# RH018_1.net
KiCad netlist of a schematic drawn in EAGLE
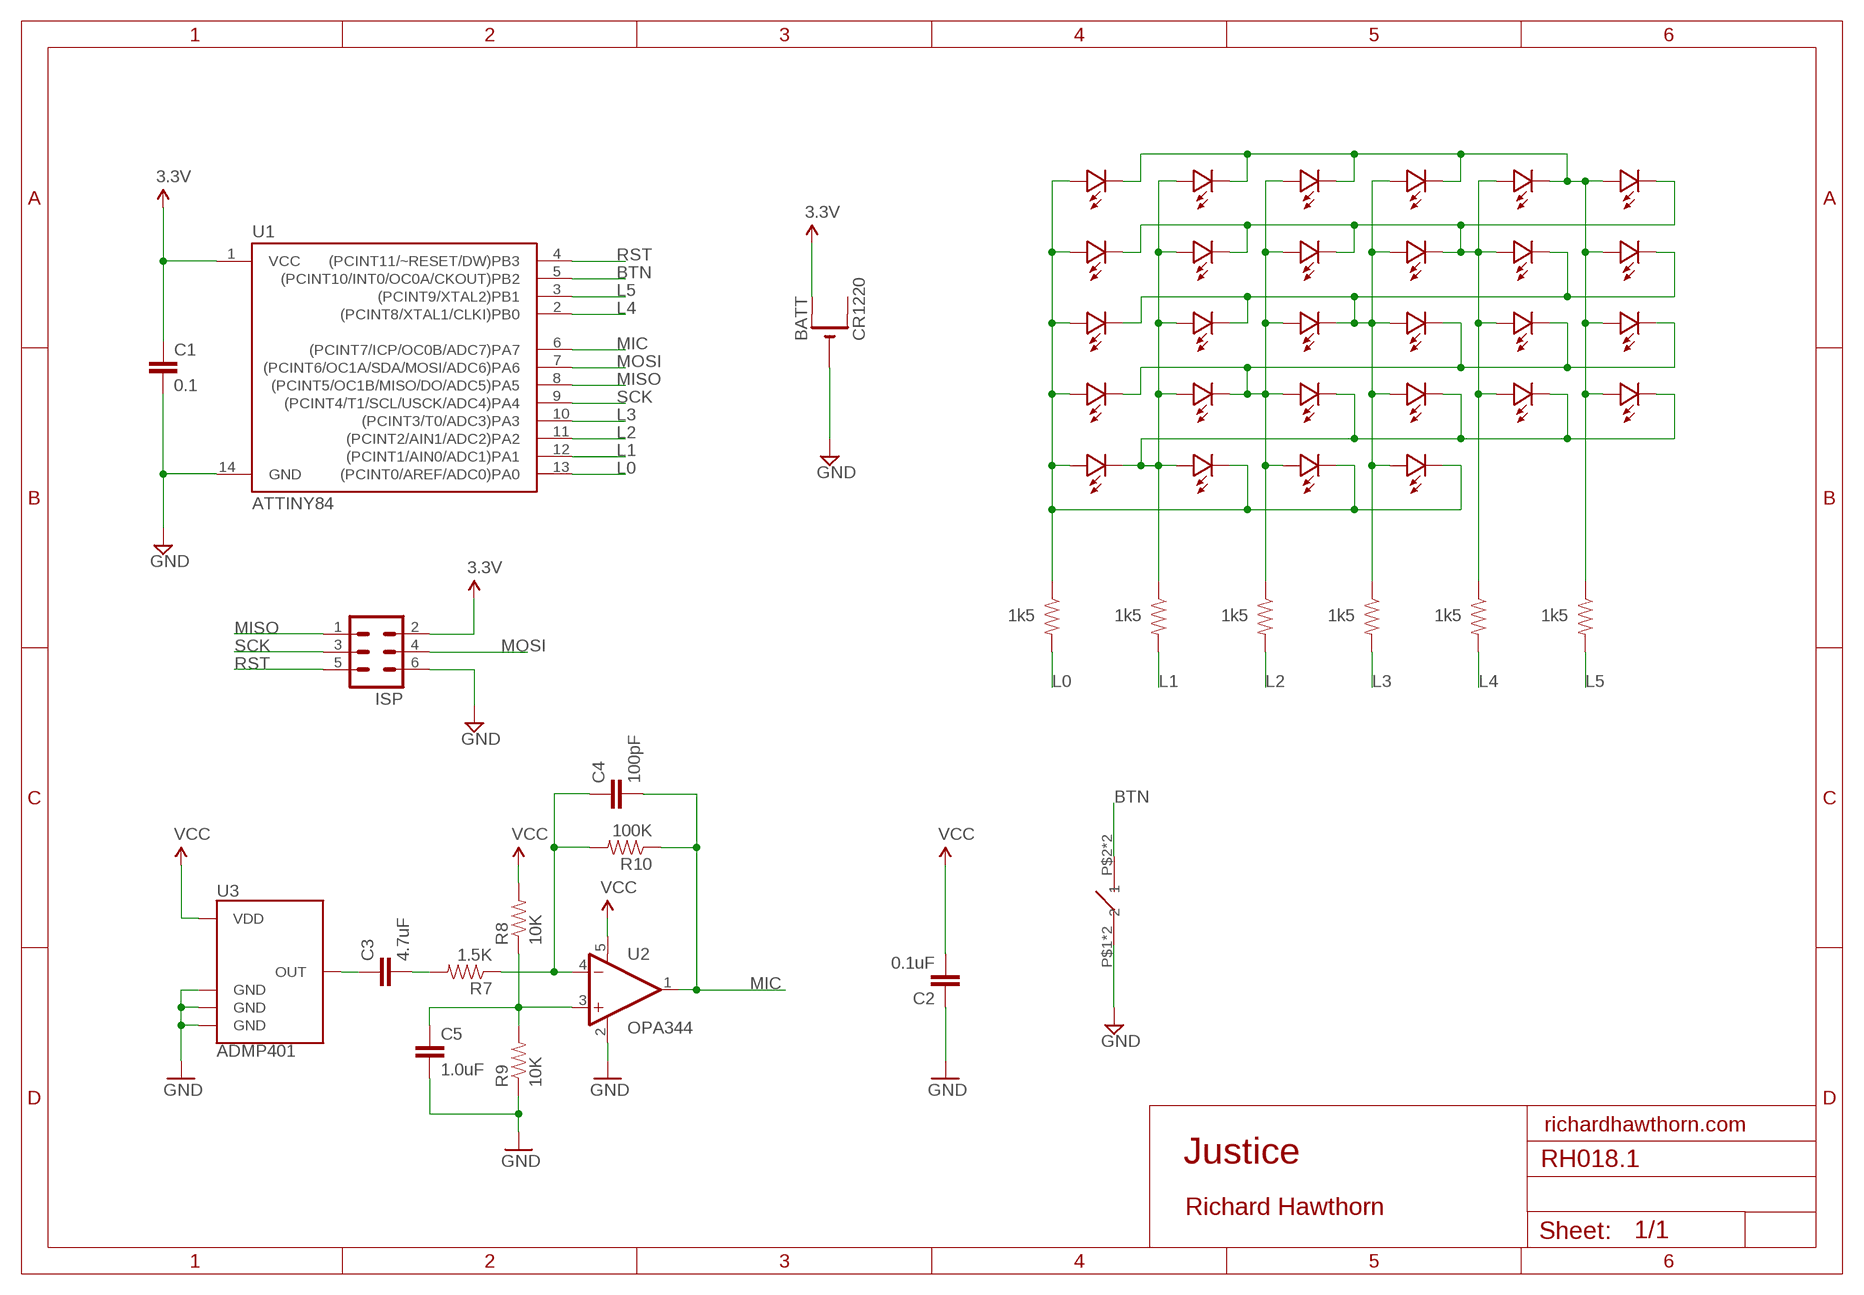
[diagram p0: schematic, sheet 1]

(export (version "E")
  (design (tool "Eeschema 10.0.6"))
  (components
    (comp (ref "BATT")
      (value "CR1220")
      (footprint "eagle-import:CR1220-SMD")
      (libsource (lib "eagle-import") (part "CR1220SMT"))
    )
    (comp (ref "BTN1")
      (value "TURTLE-3PIN")
      (footprint "eagle-import:TURTLE-3PIN")
      (libsource (lib "eagle-import") (part "TURTLE-3PIN"))
    )
    (comp (ref "C1")
      (value "0.1")
      (footprint "eagle-import:0603-CAP")
      (libsource (lib "eagle-import") (part "CAP0603-CAP"))
    )
    (comp (ref "C2")
      (value "0.1uF")
      (footprint "eagle-import:0402-CAP")
      (libsource (lib "eagle-import") (part "SparkFun_CAP0402-CAP"))
    )
    (comp (ref "C3")
      (value "4.7uF")
      (footprint "eagle-import:0402-CAP")
      (libsource (lib "eagle-import") (part "SparkFun_CAP0402-CAP"))
    )
    (comp (ref "C4")
      (value "100pF")
      (footprint "eagle-import:0402-CAP")
      (libsource (lib "eagle-import") (part "SparkFun_CAP0402-CAP"))
    )
    (comp (ref "C5")
      (value "1.0uF")
      (footprint "eagle-import:0402-CAP")
      (libsource (lib "eagle-import") (part "SparkFun_CAP0402-CAP"))
    )
    (comp (ref "ISP")
      (value "MA03-2")
      (footprint "eagle-import:MA03-2")
      (libsource (lib "eagle-import") (part "MA03-2"))
    )
    (comp (ref "LED1")
      (value "LED0603")
      (footprint "eagle-import:0603-LED")
      (libsource (lib "eagle-import") (part "LED0603"))
    )
    (comp (ref "LED2")
      (value "LED0603")
      (footprint "eagle-import:0603-LED")
      (libsource (lib "eagle-import") (part "LED0603"))
    )
    (comp (ref "LED3")
      (value "LED0603")
      (footprint "eagle-import:0603-LED")
      (libsource (lib "eagle-import") (part "LED0603"))
    )
    (comp (ref "LED4")
      (value "LED0603")
      (footprint "eagle-import:0603-LED")
      (libsource (lib "eagle-import") (part "LED0603"))
    )
    (comp (ref "LED5")
      (value "LED0603")
      (footprint "eagle-import:0603-LED")
      (libsource (lib "eagle-import") (part "LED0603"))
    )
    (comp (ref "LED6")
      (value "LED0603")
      (footprint "eagle-import:0603-LED")
      (libsource (lib "eagle-import") (part "LED0603"))
    )
    (comp (ref "LED7")
      (value "LED0603")
      (footprint "eagle-import:0603-LED")
      (libsource (lib "eagle-import") (part "LED0603"))
    )
    (comp (ref "LED8")
      (value "LED0603")
      (footprint "eagle-import:0603-LED")
      (libsource (lib "eagle-import") (part "LED0603"))
    )
    (comp (ref "LED9")
      (value "LED0603")
      (footprint "eagle-import:0603-LED")
      (libsource (lib "eagle-import") (part "LED0603"))
    )
    (comp (ref "LED10")
      (value "LED0603")
      (footprint "eagle-import:0603-LED")
      (libsource (lib "eagle-import") (part "LED0603"))
    )
    (comp (ref "LED11")
      (value "LED0603")
      (footprint "eagle-import:0603-LED")
      (libsource (lib "eagle-import") (part "LED0603"))
    )
    (comp (ref "LED12")
      (value "LED0603")
      (footprint "eagle-import:0603-LED")
      (libsource (lib "eagle-import") (part "LED0603"))
    )
    (comp (ref "LED13")
      (value "LED0603")
      (footprint "eagle-import:0603-LED")
      (libsource (lib "eagle-import") (part "LED0603"))
    )
    (comp (ref "LED14")
      (value "LED0603")
      (footprint "eagle-import:0603-LED")
      (libsource (lib "eagle-import") (part "LED0603"))
    )
    (comp (ref "LED15")
      (value "LED0603")
      (footprint "eagle-import:0603-LED")
      (libsource (lib "eagle-import") (part "LED0603"))
    )
    (comp (ref "LED16")
      (value "LED0603")
      (footprint "eagle-import:0603-LED")
      (libsource (lib "eagle-import") (part "LED0603"))
    )
    (comp (ref "LED17")
      (value "LED0603")
      (footprint "eagle-import:0603-LED")
      (libsource (lib "eagle-import") (part "LED0603"))
    )
    (comp (ref "LED18")
      (value "LED0603")
      (footprint "eagle-import:0603-LED")
      (libsource (lib "eagle-import") (part "LED0603"))
    )
    (comp (ref "LED19")
      (value "LED0603")
      (footprint "eagle-import:0603-LED")
      (libsource (lib "eagle-import") (part "LED0603"))
    )
    (comp (ref "LED20")
      (value "LED0603")
      (footprint "eagle-import:0603-LED")
      (libsource (lib "eagle-import") (part "LED0603"))
    )
    (comp (ref "LED21")
      (value "LED0603")
      (footprint "eagle-import:0603-LED")
      (libsource (lib "eagle-import") (part "LED0603"))
    )
    (comp (ref "LED22")
      (value "LED0603")
      (footprint "eagle-import:0603-LED")
      (libsource (lib "eagle-import") (part "LED0603"))
    )
    (comp (ref "LED23")
      (value "LED0603")
      (footprint "eagle-import:0603-LED")
      (libsource (lib "eagle-import") (part "LED0603"))
    )
    (comp (ref "LED24")
      (value "LED0603")
      (footprint "eagle-import:0603-LED")
      (libsource (lib "eagle-import") (part "LED0603"))
    )
    (comp (ref "LED25")
      (value "LED0603")
      (footprint "eagle-import:0603-LED")
      (libsource (lib "eagle-import") (part "LED0603"))
    )
    (comp (ref "LED26")
      (value "LED0603")
      (footprint "eagle-import:0603-LED")
      (libsource (lib "eagle-import") (part "LED0603"))
    )
    (comp (ref "LED27")
      (value "LED0603")
      (footprint "eagle-import:0603-LED")
      (libsource (lib "eagle-import") (part "LED0603"))
    )
    (comp (ref "LED28")
      (value "LED0603")
      (footprint "eagle-import:0603-LED")
      (libsource (lib "eagle-import") (part "LED0603"))
    )
    (comp (ref "R1")
      (value "1k5")
      (footprint "eagle-import:0603-RES")
      (libsource (lib "eagle-import") (part "RESISTOR0603-RES"))
    )
    (comp (ref "R2")
      (value "1k5")
      (footprint "eagle-import:0603-RES")
      (libsource (lib "eagle-import") (part "RESISTOR0603-RES"))
    )
    (comp (ref "R3")
      (value "1k5")
      (footprint "eagle-import:0603-RES")
      (libsource (lib "eagle-import") (part "RESISTOR0603-RES"))
    )
    (comp (ref "R4")
      (value "1k5")
      (footprint "eagle-import:0603-RES")
      (libsource (lib "eagle-import") (part "RESISTOR0603-RES"))
    )
    (comp (ref "R5")
      (value "1k5")
      (footprint "eagle-import:0603-RES")
      (libsource (lib "eagle-import") (part "RESISTOR0603-RES"))
    )
    (comp (ref "R6")
      (value "1k5")
      (footprint "eagle-import:0603-RES")
      (libsource (lib "eagle-import") (part "RESISTOR0603-RES"))
    )
    (comp (ref "R7")
      (value "1.5K")
      (footprint "eagle-import:0402-RES")
      (libsource (lib "eagle-import") (part "SparkFun_RESISTOR0402-RES"))
    )
    (comp (ref "R8")
      (value "10K")
      (footprint "eagle-import:0402-RES")
      (libsource (lib "eagle-import") (part "SparkFun_RESISTOR0402-RES"))
    )
    (comp (ref "R9")
      (value "10K")
      (footprint "eagle-import:0402-RES")
      (libsource (lib "eagle-import") (part "SparkFun_RESISTOR0402-RES"))
    )
    (comp (ref "R10")
      (value "100K")
      (footprint "eagle-import:0402-RES")
      (libsource (lib "eagle-import") (part "SparkFun_RESISTOR0402-RES"))
    )
    (comp (ref "U1")
      (value "ATTINY84")
      (footprint "eagle-import:SO14")
      (libsource (lib "eagle-import") (part "ATTINY84"))
    )
    (comp (ref "U2")
      (value "OPA344")
      (footprint "eagle-import:SOT23-5")
      (libsource (lib "eagle-import") (part "OPA344"))
    )
    (comp (ref "U3")
      (value "ADMP401")
      (footprint "eagle-import:ADMP401")
      (libsource (lib "eagle-import") (part "ADMP401"))
    )
  )
  (nets
    (net (code "1") (name "/BTN") (class "Default")
      (node (ref "BTN1") (pin "P$2") (pinfunction "2_P$2") (pintype "bidirectional"))
      (node (ref "BTN1") (pin "P$4") (pinfunction "2_P$4") (pintype "bidirectional"))
      (node (ref "U1") (pin "5") (pinfunction "(PCINT10/INT0/OC0A/CKOUT)PB2_5") (pintype "bidirectional"))
    )
    (net (code "2") (name "/L0") (class "Default")
      (node (ref "R1") (pin "2") (pinfunction "2_2") (pintype "passive"))
      (node (ref "U1") (pin "13") (pinfunction "(PCINT0/AREF/ADC0)PA0_13") (pintype "bidirectional"))
    )
    (net (code "3") (name "/L1") (class "Default")
      (node (ref "R2") (pin "2") (pinfunction "2_2") (pintype "passive"))
      (node (ref "U1") (pin "12") (pinfunction "(PCINT1/AIN0/ADC1)PA1_12") (pintype "bidirectional"))
    )
    (net (code "4") (name "/L2") (class "Default")
      (node (ref "R3") (pin "2") (pinfunction "2_2") (pintype "passive"))
      (node (ref "U1") (pin "11") (pinfunction "(PCINT2/AIN1/ADC2)PA2_11") (pintype "bidirectional"))
    )
    (net (code "5") (name "/L3") (class "Default")
      (node (ref "R4") (pin "2") (pinfunction "2_2") (pintype "passive"))
      (node (ref "U1") (pin "10") (pinfunction "(PCINT3/T0/ADC3)PA3_10") (pintype "bidirectional"))
    )
    (net (code "6") (name "/L4") (class "Default")
      (node (ref "R5") (pin "2") (pinfunction "2_2") (pintype "passive"))
      (node (ref "U1") (pin "2") (pinfunction "(PCINT8/XTAL1/CLKI)PB0_2") (pintype "bidirectional"))
    )
    (net (code "7") (name "/L5") (class "Default")
      (node (ref "R6") (pin "2") (pinfunction "2_2") (pintype "passive"))
      (node (ref "U1") (pin "3") (pinfunction "(PCINT9/XTAL2)PB1_3") (pintype "bidirectional"))
    )
    (net (code "8") (name "/MIC") (class "Default")
      (node (ref "C4") (pin "2") (pinfunction "2_2") (pintype "passive"))
      (node (ref "R10") (pin "1") (pinfunction "1_1") (pintype "passive"))
      (node (ref "U1") (pin "6") (pinfunction "(PCINT7/ICP/OC0B/ADC7)PA7_6") (pintype "bidirectional"))
      (node (ref "U2") (pin "1") (pinfunction "OUT_1") (pintype "output"))
    )
    (net (code "9") (name "/MISO") (class "Default")
      (node (ref "ISP") (pin "1") (pinfunction "1_1") (pintype "passive"))
      (node (ref "U1") (pin "8") (pinfunction "(PCINT5/OC1B/MISO/DO/ADC5)PA5_8") (pintype "bidirectional"))
    )
    (net (code "10") (name "/MOSI") (class "Default")
      (node (ref "ISP") (pin "4") (pinfunction "4_4") (pintype "passive"))
      (node (ref "U1") (pin "7") (pinfunction "(PCINT6/OC1A/SDA/MOSI/ADC6)PA6_7") (pintype "bidirectional"))
    )
    (net (code "11") (name "/RST") (class "Default")
      (node (ref "ISP") (pin "5") (pinfunction "5_5") (pintype "passive"))
      (node (ref "U1") (pin "4") (pinfunction "(PCINT11/~{RESET/DW})PB3_4") (pintype "bidirectional"))
    )
    (net (code "12") (name "/SCK") (class "Default")
      (node (ref "ISP") (pin "3") (pinfunction "3_3") (pintype "passive"))
      (node (ref "U1") (pin "9") (pinfunction "(PCINT4/T1/SCL/USCK/ADC4)PA4_9") (pintype "bidirectional"))
    )
    (net (code "13") (name "3.3V") (class "Default")
      (node (ref "BATT") (pin "+$1") (pinfunction "+_+$1") (pintype "passive"))
      (node (ref "C1") (pin "1") (pinfunction "1_1") (pintype "passive"))
      (node (ref "C2") (pin "2") (pinfunction "2_2") (pintype "passive"))
      (node (ref "ISP") (pin "2") (pinfunction "2_2") (pintype "passive"))
      (node (ref "R8") (pin "2") (pinfunction "2_2") (pintype "passive"))
      (node (ref "U1") (pin "1") (pinfunction "VCC_1") (pintype "bidirectional"))
      (node (ref "U2") (pin "5") (pinfunction "V+_5") (pintype "power_in"))
      (node (ref "U3") (pin "5") (pinfunction "VDD_5") (pintype "bidirectional"))
    )
    (net (code "14") (name "GND") (class "Default")
      (node (ref "BATT") (pin "-") (pinfunction "-_-") (pintype "passive"))
      (node (ref "BTN1") (pin "P$1") (pinfunction "1_P$1") (pintype "bidirectional"))
      (node (ref "BTN1") (pin "P$3") (pinfunction "1_P$3") (pintype "bidirectional"))
      (node (ref "C1") (pin "2") (pinfunction "2_2") (pintype "passive"))
      (node (ref "C2") (pin "1") (pinfunction "1_1") (pintype "passive"))
      (node (ref "C5") (pin "2") (pinfunction "2_2") (pintype "passive"))
      (node (ref "ISP") (pin "6") (pinfunction "6_6") (pintype "passive"))
      (node (ref "R9") (pin "1") (pinfunction "1_1") (pintype "passive"))
      (node (ref "U1") (pin "14") (pinfunction "GND_14") (pintype "bidirectional"))
      (node (ref "U2") (pin "2") (pinfunction "V-_2") (pintype "power_in"))
      (node (ref "U3") (pin "2") (pinfunction "GND_2") (pintype "bidirectional"))
      (node (ref "U3") (pin "4") (pinfunction "GND_4") (pintype "bidirectional"))
      (node (ref "U3") (pin "6") (pinfunction "GND_6") (pintype "bidirectional"))
    )
    (net (code "15") (name "Net-(C3-Pad2)") (class "Default")
      (node (ref "C3") (pin "2") (pinfunction "2_2") (pintype "passive"))
      (node (ref "R7") (pin "2") (pinfunction "2_2") (pintype "passive"))
    )
    (net (code "16") (name "Net-(LED1-PadMINUS)") (class "Default")
      (node (ref "LED1") (pin "MINUS") (pinfunction "MINUS_MINUS") (pintype "passive"))
      (node (ref "LED12") (pin "PLUS") (pinfunction "PLUS_PLUS") (pintype "passive"))
      (node (ref "LED18") (pin "PLUS") (pinfunction "PLUS_PLUS") (pintype "passive"))
      (node (ref "LED2") (pin "MINUS") (pinfunction "MINUS_MINUS") (pintype "passive"))
      (node (ref "LED24") (pin "PLUS") (pinfunction "PLUS_PLUS") (pintype "passive"))
      (node (ref "LED3") (pin "MINUS") (pinfunction "MINUS_MINUS") (pintype "passive"))
      (node (ref "LED4") (pin "MINUS") (pinfunction "MINUS_MINUS") (pintype "passive"))
      (node (ref "LED5") (pin "MINUS") (pinfunction "MINUS_MINUS") (pintype "passive"))
      (node (ref "LED6") (pin "PLUS") (pinfunction "PLUS_PLUS") (pintype "passive"))
      (node (ref "R6") (pin "1") (pinfunction "1_1") (pintype "passive"))
    )
    (net (code "17") (name "Net-(LED1-PadPLUS)") (class "Default")
      (node (ref "LED1") (pin "PLUS") (pinfunction "PLUS_PLUS") (pintype "passive"))
      (node (ref "LED13") (pin "PLUS") (pinfunction "PLUS_PLUS") (pintype "passive"))
      (node (ref "LED19") (pin "PLUS") (pinfunction "PLUS_PLUS") (pintype "passive"))
      (node (ref "LED25") (pin "PLUS") (pinfunction "PLUS_PLUS") (pintype "passive"))
      (node (ref "LED26") (pin "MINUS") (pinfunction "MINUS_MINUS") (pintype "passive"))
      (node (ref "LED27") (pin "MINUS") (pinfunction "MINUS_MINUS") (pintype "passive"))
      (node (ref "LED28") (pin "MINUS") (pinfunction "MINUS_MINUS") (pintype "passive"))
      (node (ref "LED7") (pin "PLUS") (pinfunction "PLUS_PLUS") (pintype "passive"))
      (node (ref "R1") (pin "1") (pinfunction "1_1") (pintype "passive"))
    )
    (net (code "18") (name "Net-(LED10-PadMINUS)") (class "Default")
      (node (ref "LED10") (pin "MINUS") (pinfunction "MINUS_MINUS") (pintype "passive"))
      (node (ref "LED11") (pin "PLUS") (pinfunction "PLUS_PLUS") (pintype "passive"))
      (node (ref "LED17") (pin "PLUS") (pinfunction "PLUS_PLUS") (pintype "passive"))
      (node (ref "LED23") (pin "PLUS") (pinfunction "PLUS_PLUS") (pintype "passive"))
      (node (ref "LED5") (pin "PLUS") (pinfunction "PLUS_PLUS") (pintype "passive"))
      (node (ref "LED6") (pin "MINUS") (pinfunction "MINUS_MINUS") (pintype "passive"))
      (node (ref "LED7") (pin "MINUS") (pinfunction "MINUS_MINUS") (pintype "passive"))
      (node (ref "LED8") (pin "MINUS") (pinfunction "MINUS_MINUS") (pintype "passive"))
      (node (ref "LED9") (pin "MINUS") (pinfunction "MINUS_MINUS") (pintype "passive"))
      (node (ref "R5") (pin "1") (pinfunction "1_1") (pintype "passive"))
    )
    (net (code "19") (name "Net-(LED10-PadPLUS)") (class "Default")
      (node (ref "LED10") (pin "PLUS") (pinfunction "PLUS_PLUS") (pintype "passive"))
      (node (ref "LED11") (pin "MINUS") (pinfunction "MINUS_MINUS") (pintype "passive"))
      (node (ref "LED12") (pin "MINUS") (pinfunction "MINUS_MINUS") (pintype "passive"))
      (node (ref "LED13") (pin "MINUS") (pinfunction "MINUS_MINUS") (pintype "passive"))
      (node (ref "LED14") (pin "MINUS") (pinfunction "MINUS_MINUS") (pintype "passive"))
      (node (ref "LED15") (pin "MINUS") (pinfunction "MINUS_MINUS") (pintype "passive"))
      (node (ref "LED16") (pin "PLUS") (pinfunction "PLUS_PLUS") (pintype "passive"))
      (node (ref "LED22") (pin "PLUS") (pinfunction "PLUS_PLUS") (pintype "passive"))
      (node (ref "LED28") (pin "PLUS") (pinfunction "PLUS_PLUS") (pintype "passive"))
      (node (ref "LED4") (pin "PLUS") (pinfunction "PLUS_PLUS") (pintype "passive"))
      (node (ref "R4") (pin "1") (pinfunction "1_1") (pintype "passive"))
    )
    (net (code "20") (name "Net-(LED14-PadPLUS)") (class "Default")
      (node (ref "LED14") (pin "PLUS") (pinfunction "PLUS_PLUS") (pintype "passive"))
      (node (ref "LED2") (pin "PLUS") (pinfunction "PLUS_PLUS") (pintype "passive"))
      (node (ref "LED20") (pin "PLUS") (pinfunction "PLUS_PLUS") (pintype "passive"))
      (node (ref "LED21") (pin "MINUS") (pinfunction "MINUS_MINUS") (pintype "passive"))
      (node (ref "LED22") (pin "MINUS") (pinfunction "MINUS_MINUS") (pintype "passive"))
      (node (ref "LED23") (pin "MINUS") (pinfunction "MINUS_MINUS") (pintype "passive"))
      (node (ref "LED24") (pin "MINUS") (pinfunction "MINUS_MINUS") (pintype "passive"))
      (node (ref "LED25") (pin "MINUS") (pinfunction "MINUS_MINUS") (pintype "passive"))
      (node (ref "LED26") (pin "PLUS") (pinfunction "PLUS_PLUS") (pintype "passive"))
      (node (ref "LED8") (pin "PLUS") (pinfunction "PLUS_PLUS") (pintype "passive"))
      (node (ref "R2") (pin "1") (pinfunction "1_1") (pintype "passive"))
    )
    (net (code "21") (name "Net-(LED15-PadPLUS)") (class "Default")
      (node (ref "LED15") (pin "PLUS") (pinfunction "PLUS_PLUS") (pintype "passive"))
      (node (ref "LED16") (pin "MINUS") (pinfunction "MINUS_MINUS") (pintype "passive"))
      (node (ref "LED17") (pin "MINUS") (pinfunction "MINUS_MINUS") (pintype "passive"))
      (node (ref "LED18") (pin "MINUS") (pinfunction "MINUS_MINUS") (pintype "passive"))
      (node (ref "LED19") (pin "MINUS") (pinfunction "MINUS_MINUS") (pintype "passive"))
      (node (ref "LED20") (pin "MINUS") (pinfunction "MINUS_MINUS") (pintype "passive"))
      (node (ref "LED21") (pin "PLUS") (pinfunction "PLUS_PLUS") (pintype "passive"))
      (node (ref "LED27") (pin "PLUS") (pinfunction "PLUS_PLUS") (pintype "passive"))
      (node (ref "LED3") (pin "PLUS") (pinfunction "PLUS_PLUS") (pintype "passive"))
      (node (ref "LED9") (pin "PLUS") (pinfunction "PLUS_PLUS") (pintype "passive"))
      (node (ref "R3") (pin "1") (pinfunction "1_1") (pintype "passive"))
    )
    (net (code "22") (name "Net-(U2-+IN)") (class "Default")
      (node (ref "C5") (pin "1") (pinfunction "1_1") (pintype "passive"))
      (node (ref "R8") (pin "1") (pinfunction "1_1") (pintype "passive"))
      (node (ref "R9") (pin "2") (pinfunction "2_2") (pintype "passive"))
      (node (ref "U2") (pin "3") (pinfunction "+IN_3") (pintype "input"))
    )
    (net (code "23") (name "Net-(U2--IN)") (class "Default")
      (node (ref "C4") (pin "1") (pinfunction "1_1") (pintype "passive"))
      (node (ref "R10") (pin "2") (pinfunction "2_2") (pintype "passive"))
      (node (ref "R7") (pin "1") (pinfunction "1_1") (pintype "passive"))
      (node (ref "U2") (pin "4") (pinfunction "-IN_4") (pintype "input"))
    )
    (net (code "24") (name "Net-(U3-OUT)") (class "Default")
      (node (ref "C3") (pin "1") (pinfunction "1_1") (pintype "passive"))
      (node (ref "U3") (pin "1") (pinfunction "OUT_1") (pintype "bidirectional"))
    )
    (net (code "25") (name "unconnected-(BATT-+1-Pad+$2)") (class "Default")
      (node (ref "BATT") (pin "+$2") (pinfunction "+1_+$2") (pintype "passive"))
    )
  )
)
